# SCH_MinijetengineECU_20260723.net
KiCad netlist of a schematic drawn in EasyEDA
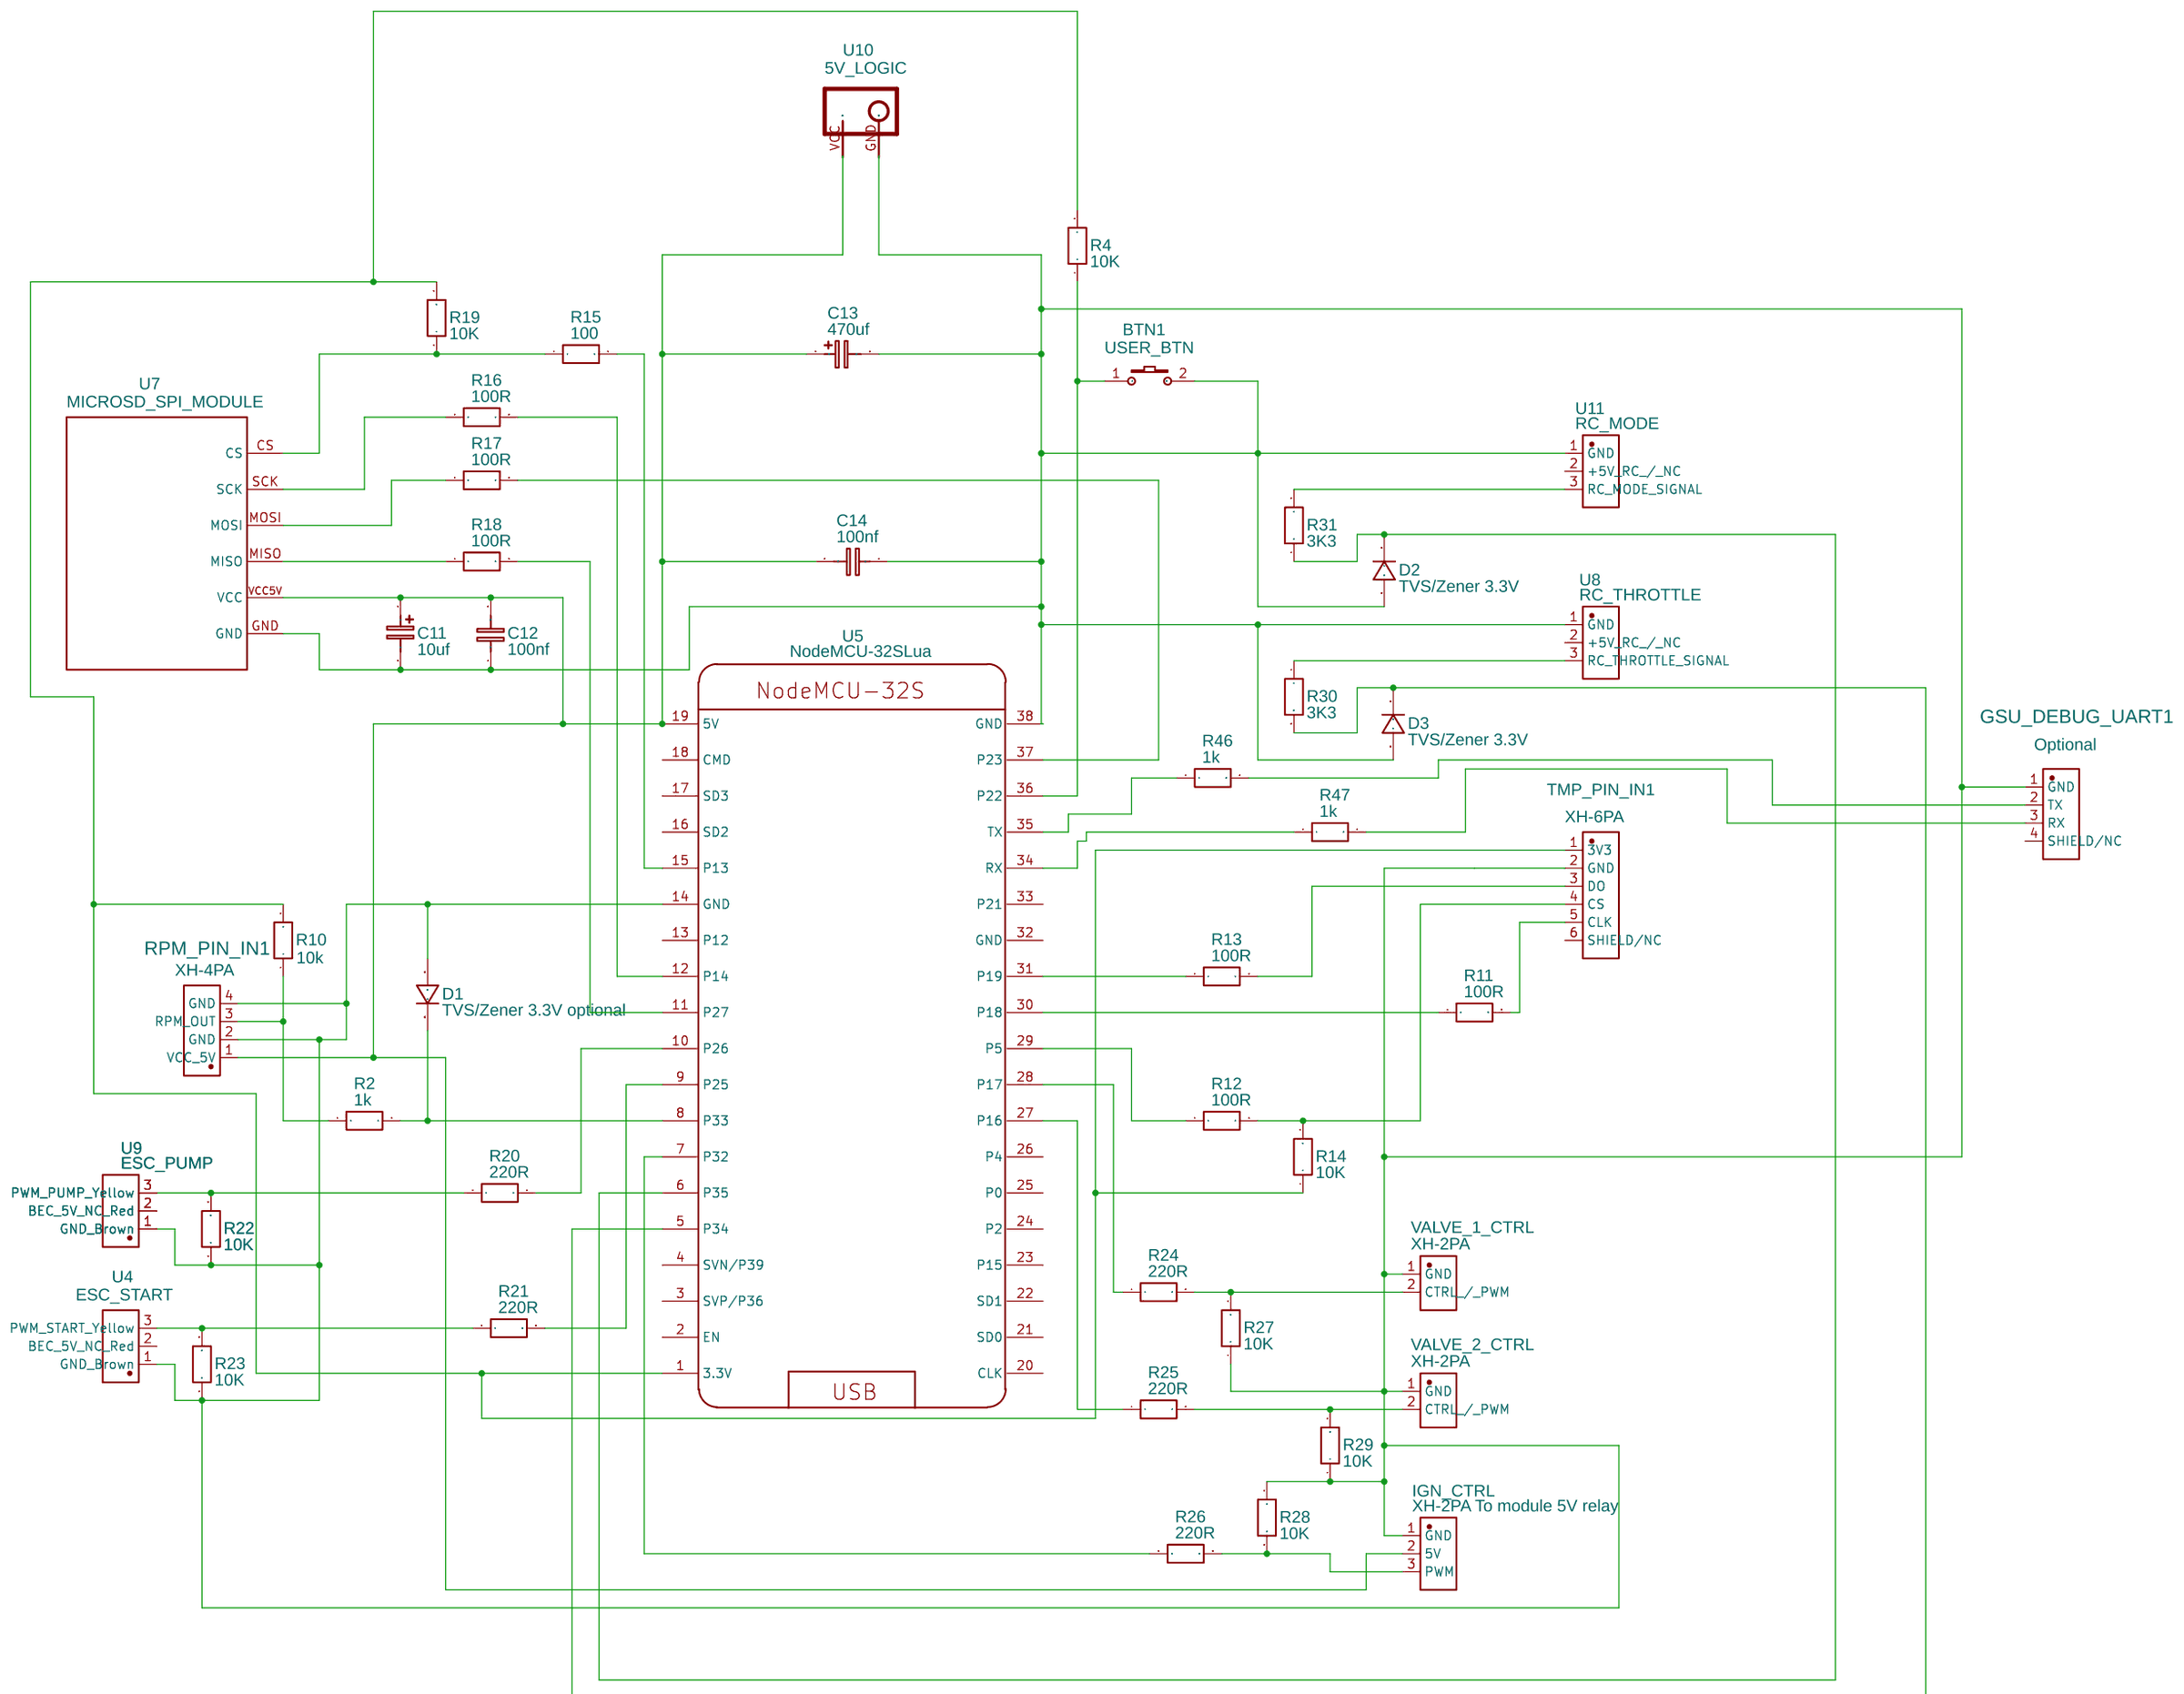
[diagram p0: ECU_JET]
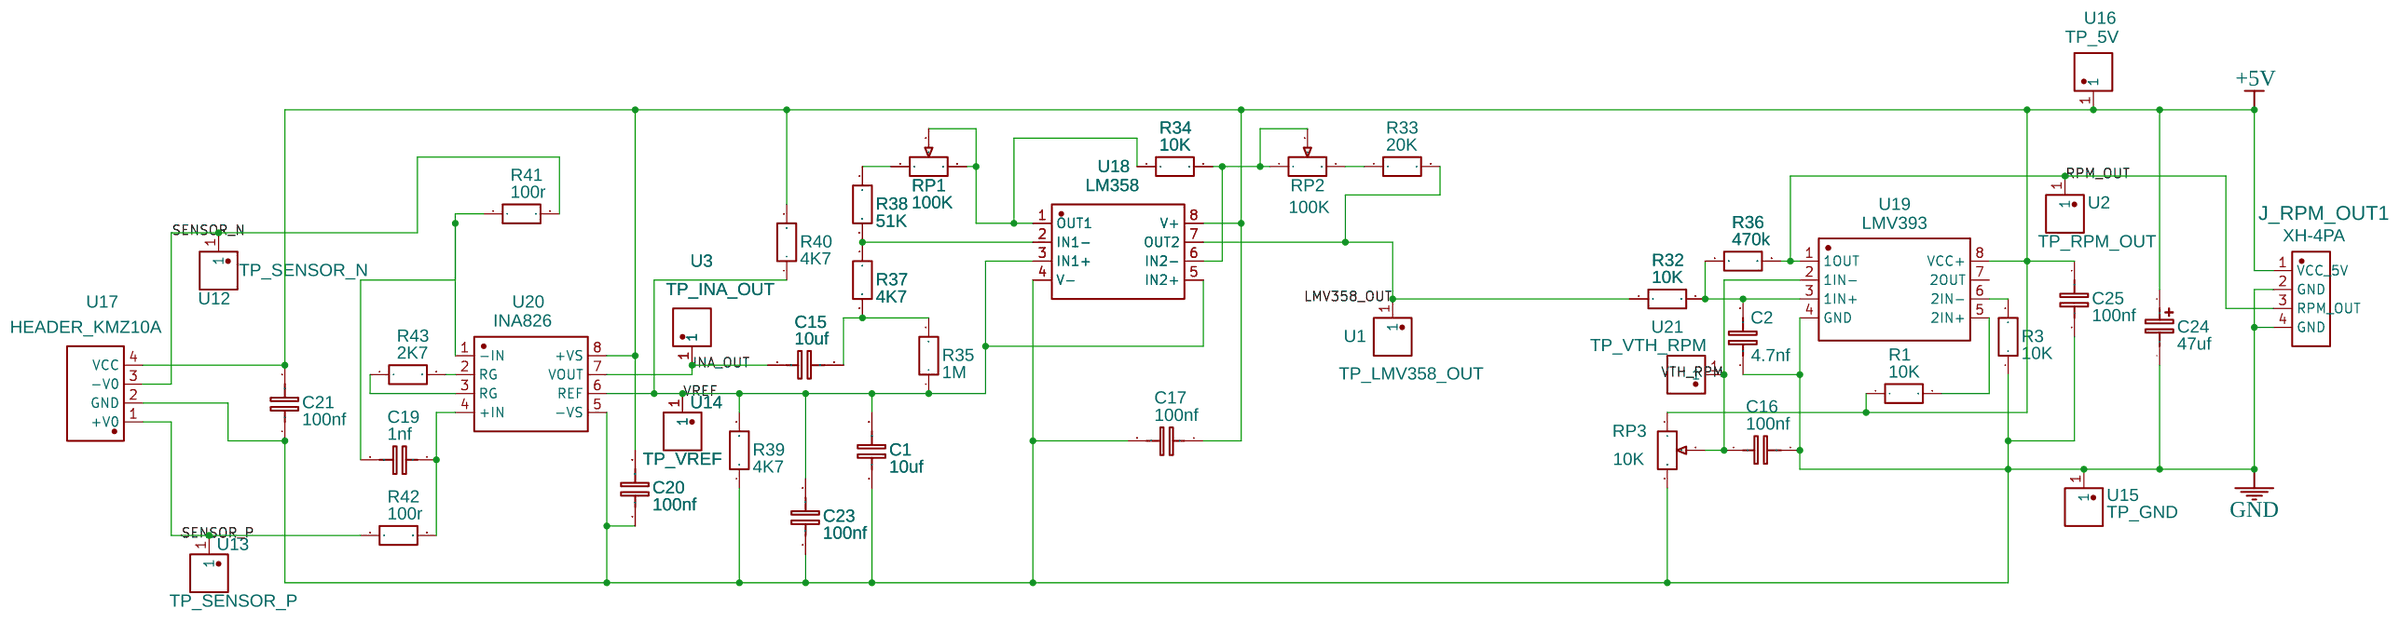
[diagram p1: RPM_Sensor]
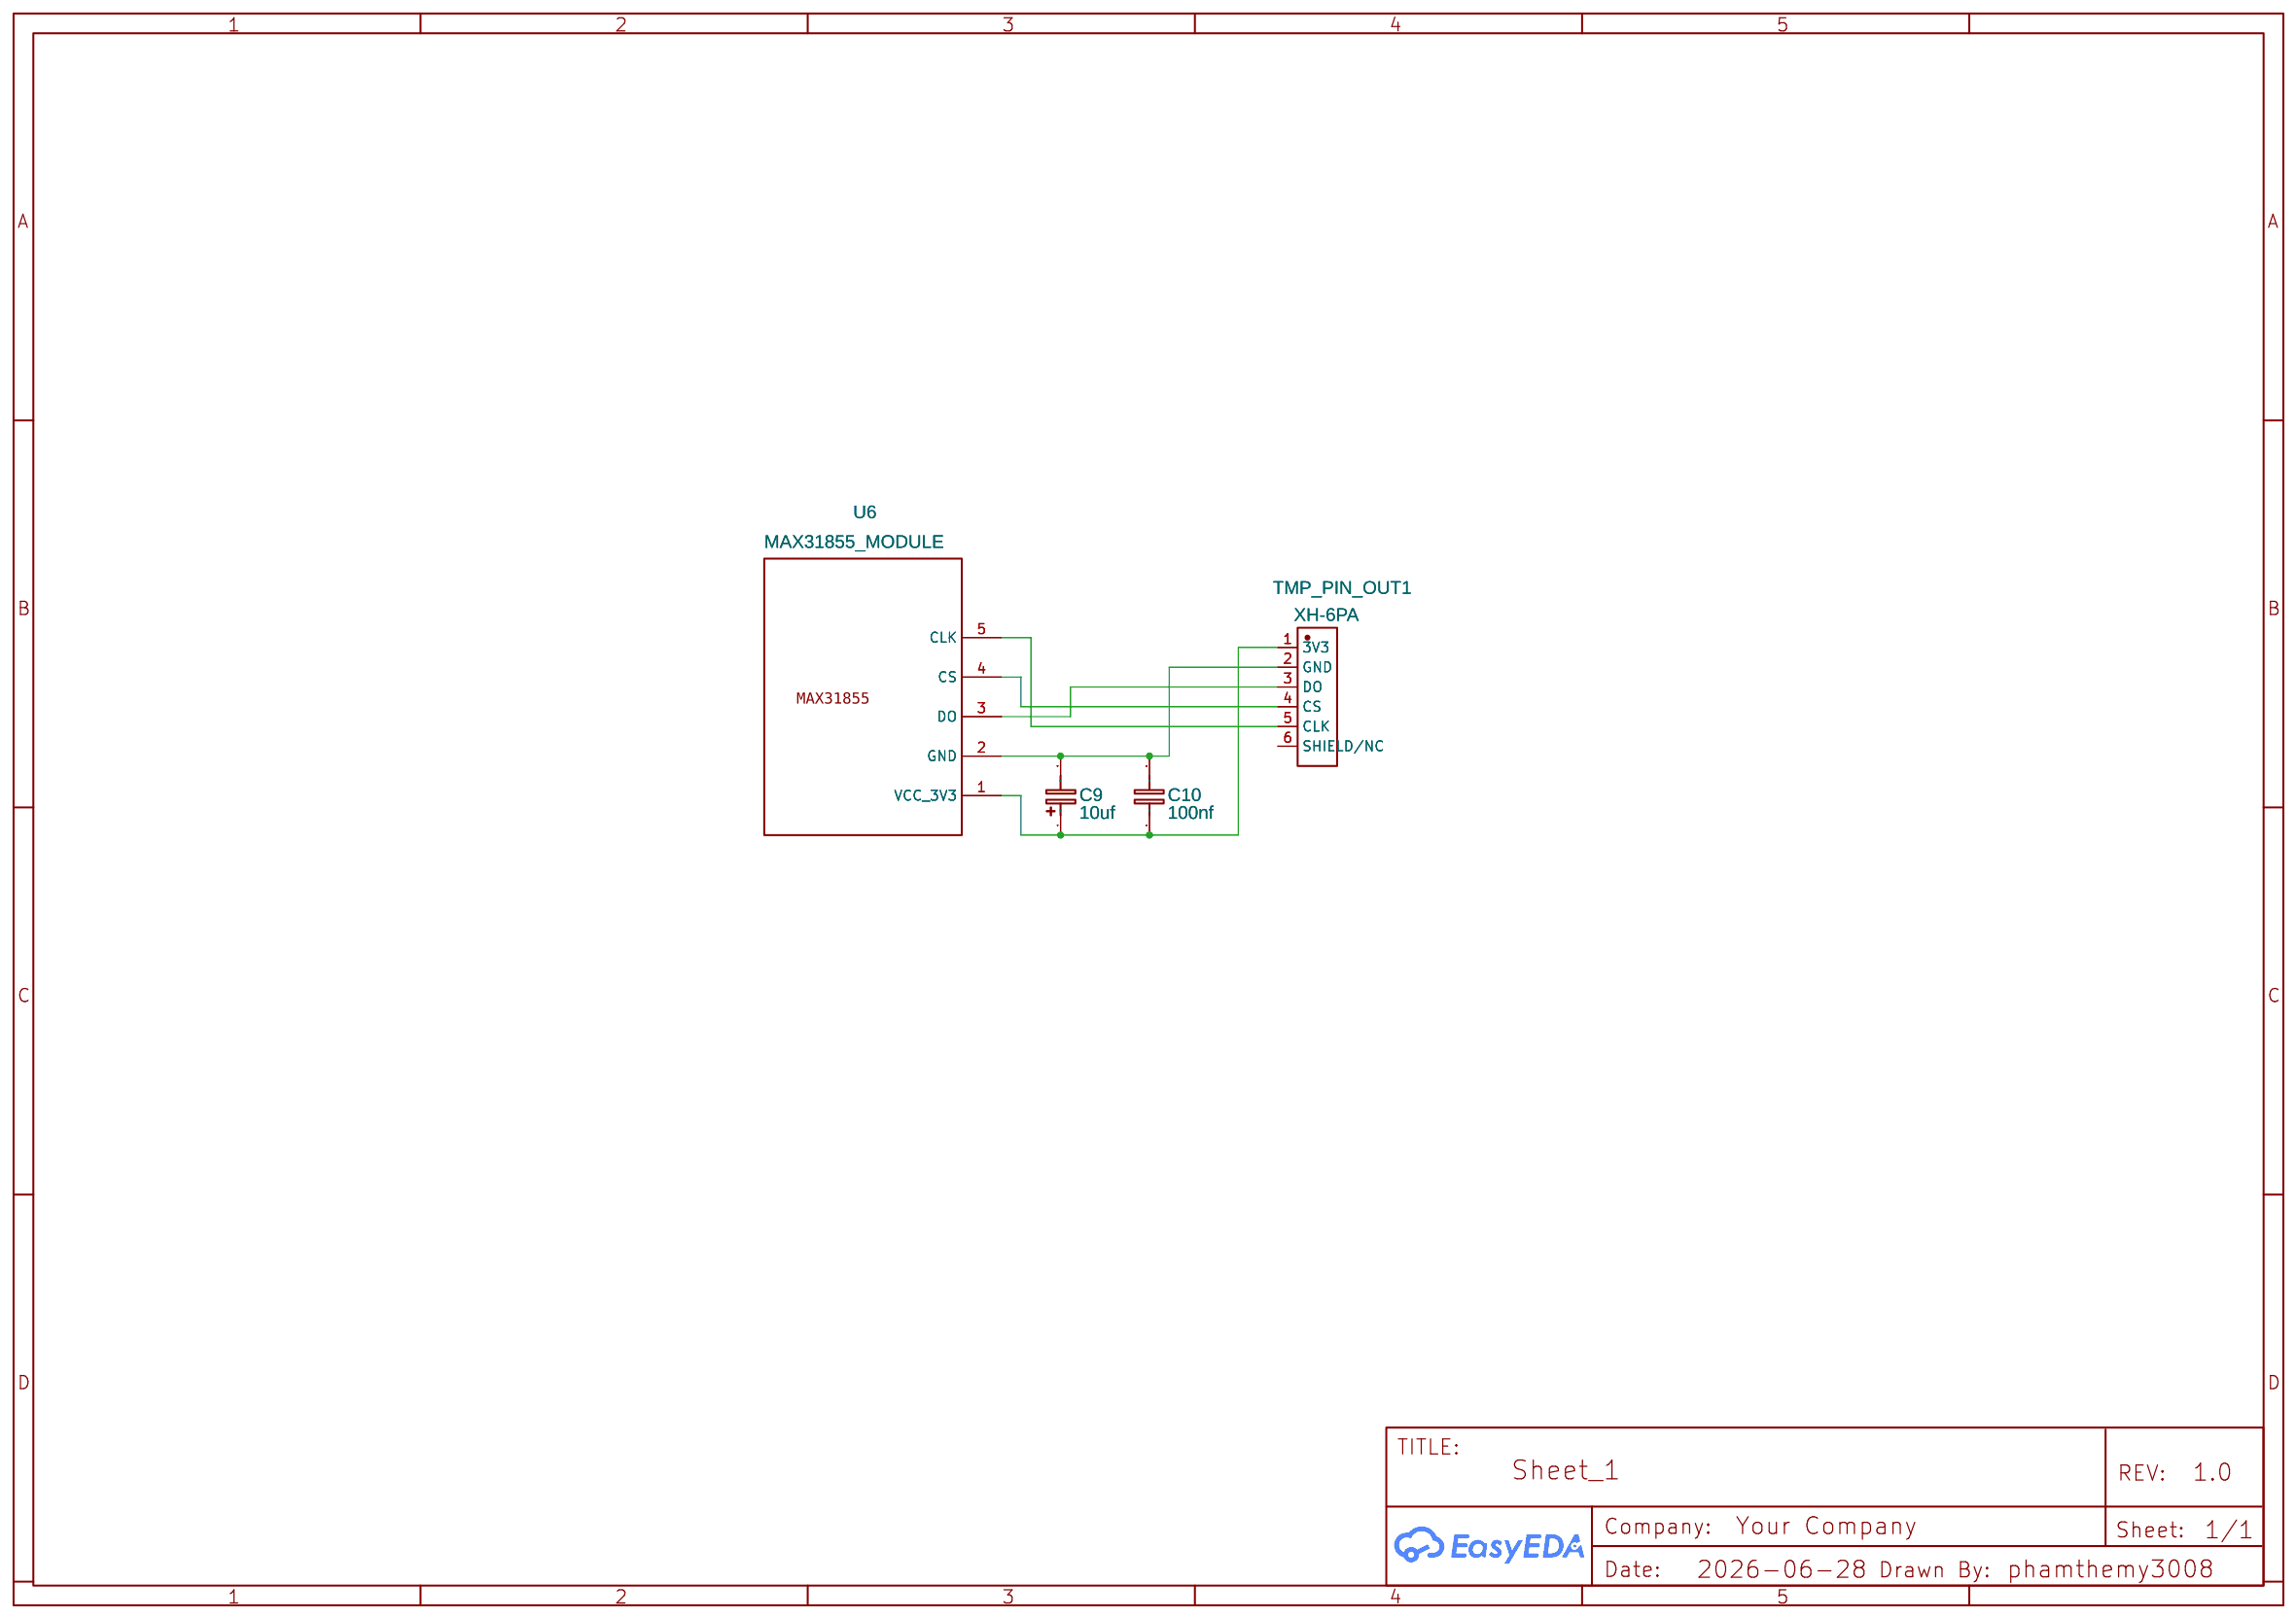
[diagram p2: Temperature_Sensor]

(export (version "E")
  (design (tool "Eeschema 10.0.6"))
  (components
    (comp (ref "BTN1")
      (value "USER_BTN")
      (fields (field (name "Manufacturer Part") "K2-1107ST-A4SW-06"))
      (libsource (lib "") (part "K2-3.6×6.1_SMD"))
    )
    (comp (ref "C11") (value "10uf") (libsource (lib "") (part "C_Tan_SMD_A_EU")))
    (comp (ref "C12") (value "100nf") (libsource (lib "") (part "C_0603_EU")))
    (comp (ref "C13") (value "470uf") (libsource (lib "") (part "C_Tan_SMD_A_EU_1")))
    (comp (ref "C14") (value "100nf") (libsource (lib "") (part "C_0603_EU_1")))
    (comp (ref "D1") (value "TVS/Zener 3.3V optional") (libsource (lib "") (part "1N4007W_1")))
    (comp (ref "D2") (value "TVS/Zener 3.3V") (libsource (lib "") (part "1N4007W")))
    (comp (ref "D3") (value "TVS/Zener 3.3V") (libsource (lib "") (part "1N4007W")))
    (comp (ref "GSU_DEBUG_UART1")
      (value "Optional")
      (fields (field (name "Manufacturer Part") "XH-4PA") (field (name "Manufacturer") "ZHOURI(洲日)"))
      (libsource (lib "") (part "XH-4PA"))
    )
    (comp (ref "IGN_CTRL")
      (value "XH-2PA To module 5V relay")
      (fields (field (name "Manufacturer Part") "Header35.08-3P"))
      (libsource (lib "") (part "HEADER35.08-3P_1"))
    )
    (comp (ref "R2") (value "1k") (libsource (lib "") (part "R_0603_EU")))
    (comp (ref "R4") (value "10K") (libsource (lib "") (part "R_0603_EU_2")))
    (comp (ref "R10") (value "10k") (libsource (lib "") (part "R_0603_EU_2")))
    (comp (ref "R11") (value "100R") (libsource (lib "") (part "R_0603_EU")))
    (comp (ref "R12") (value "100R") (libsource (lib "") (part "R_0603_EU")))
    (comp (ref "R13") (value "100R") (libsource (lib "") (part "R_0603_EU")))
    (comp (ref "R14") (value "10K") (libsource (lib "") (part "R_0603_EU_2")))
    (comp (ref "R15") (value "100") (libsource (lib "") (part "R_0603_EU")))
    (comp (ref "R16") (value "100R") (libsource (lib "") (part "R_0603_EU")))
    (comp (ref "R17") (value "100R") (libsource (lib "") (part "R_0603_EU")))
    (comp (ref "R18") (value "100R") (libsource (lib "") (part "R_0603_EU")))
    (comp (ref "R19") (value "10K") (libsource (lib "") (part "R_0603_EU_2")))
    (comp (ref "R20") (value "220R") (libsource (lib "") (part "R_0603_EU")))
    (comp (ref "R21") (value "220R") (libsource (lib "") (part "R_0603_EU")))
    (comp (ref "R22") (value "10K") (libsource (lib "") (part "R_0603_EU_2")))
    (comp (ref "R23") (value "10K") (libsource (lib "") (part "R_0603_EU_2")))
    (comp (ref "R24") (value "220R") (libsource (lib "") (part "R_0603_EU")))
    (comp (ref "R25") (value "220R") (libsource (lib "") (part "R_0603_EU")))
    (comp (ref "R26") (value "220R") (libsource (lib "") (part "R_0603_EU")))
    (comp (ref "R27") (value "10K") (libsource (lib "") (part "R_0603_EU_2")))
    (comp (ref "R28") (value "10K") (libsource (lib "") (part "R_0603_EU_1")))
    (comp (ref "R29") (value "10K") (libsource (lib "") (part "R_0603_EU_2")))
    (comp (ref "R30") (value "3K3") (libsource (lib "") (part "R_0603_EU_1")))
    (comp (ref "R31") (value "3K3") (libsource (lib "") (part "R_0603_EU_2")))
    (comp (ref "R46") (value "1k") (libsource (lib "") (part "R_0603_EU")))
    (comp (ref "R47") (value "1k") (libsource (lib "") (part "R_0603_EU")))
    (comp (ref "RPM_PIN_IN1")
      (value "XH-4PA")
      (fields (field (name "Manufacturer") "ZHOURI(洲日)"))
      (libsource (lib "") (part "XH-4PA_1"))
    )
    (comp (ref "TMP_PIN_IN1")
      (value "XH-6PA")
      (fields (field (name "Manufacturer") "ZHOURI(洲日)"))
      (libsource (lib "") (part "XH-6PA"))
    )
    (comp (ref "U4")
      (value "ESC_START")
      (fields (field (name "Manufacturer Part") "Header35.08-3P"))
      (libsource (lib "") (part "HEADER35.08-3P"))
    )
    (comp (ref "U5")
      (value "NodeMCU-32SLua")
      (fields (field (name "Manufacturer") "Ai-Thinker"))
      (libsource (lib "") (part "NodeMCU-32SLua"))
    )
    (comp (ref "U7") (value "MICROSD_SPI_MODULE") (libsource (lib "") (part "MICROSD_SPI_MODULE")))
    (comp (ref "U8")
      (value "RC_THROTTLE")
      (fields (field (name "Manufacturer Part") "Header35.08-3P"))
      (libsource (lib "") (part "HEADER35.08-3P_2"))
    )
    (comp (ref "U9")
      (value "ESC_PUMP")
      (fields (field (name "Manufacturer Part") "Header35.08-3P"))
      (libsource (lib "") (part "HEADER35.08-3P_3"))
    )
    (comp (ref "U10") (value "5V_LOGIC") (libsource (lib "") (part "DOMINO-2P-5.08")))
    (comp (ref "U11")
      (value "RC_MODE")
      (fields (field (name "Manufacturer Part") "Header35.08-3P"))
      (libsource (lib "") (part "HEADER35.08-3P_4"))
    )
    (comp (ref "VALVE_1_CTRL")
      (value "XH-2PA")
      (fields (field (name "Manufacturer") "ZHOURI(洲日)"))
      (libsource (lib "") (part "XH-2PA_1"))
    )
    (comp (ref "VALVE_2_CTRL")
      (value "XH-2PA")
      (fields (field (name "Manufacturer") "ZHOURI(洲日)"))
      (libsource (lib "") (part "XH-2PA"))
    )
    (comp (ref "C1") (value "10uf") (libsource (lib "") (part "C_0603_EU_2")))
    (comp (ref "C2") (value "4.7nf") (libsource (lib "") (part "C_0603_EU_6")))
    (comp (ref "C15") (value "10uf") (libsource (lib "") (part "C_0603_EU_3")))
    (comp (ref "C16") (value "100nf") (libsource (lib "") (part "C_0603_EU")))
    (comp (ref "C17") (value "100nf") (libsource (lib "") (part "C_0603_EU_4")))
    (comp (ref "C19") (value "1nf") (libsource (lib "") (part "C_0603_EU_5")))
    (comp (ref "C20") (value "100nf") (libsource (lib "") (part "C_0603_EU_2")))
    (comp (ref "C21") (value "100nf") (libsource (lib "") (part "C_0603_EU_2")))
    (comp (ref "C23") (value "100nf") (libsource (lib "") (part "C_0603_EU_2")))
    (comp (ref "C24")
      (value "47uf")
      (fields (field (name "Manufacturer Part") "TAJB476K010RNJ") (field (name "Manufacturer") "Kyocera AVX"))
      (libsource (lib "") (part "C_Tan_SMD_A_EU"))
    )
    (comp (ref "C25") (value "100nf") (libsource (lib "") (part "C_0603_EU_1")))
    (comp (ref "J_RPM_OUT1")
      (value "XH-4PA")
      (fields (field (name "Manufacturer") "ZHOURI(洲日)"))
      (libsource (lib "") (part "XH-4PA"))
    )
    (comp (ref "R1") (value "10K") (libsource (lib "") (part "R_0603_EU")))
    (comp (ref "R3") (value "10K") (libsource (lib "") (part "R_0603_EU_1")))
    (comp (ref "R32") (value "10K") (libsource (lib "") (part "R_0603_EU")))
    (comp (ref "R33") (value "20K") (libsource (lib "") (part "R_0603_EU")))
    (comp (ref "R34") (value "10K") (libsource (lib "") (part "R_0603_EU")))
    (comp (ref "R35") (value "1M") (libsource (lib "") (part "R_0603_EU_1")))
    (comp (ref "R36") (value "470k") (libsource (lib "") (part "R_0603_EU")))
    (comp (ref "R37") (value "4K7") (libsource (lib "") (part "R_0603_EU_2")))
    (comp (ref "R38") (value "51K") (libsource (lib "") (part "R_0603_EU_2")))
    (comp (ref "R39") (value "4K7") (libsource (lib "") (part "R_0603_EU_1")))
    (comp (ref "R40") (value "4K7") (libsource (lib "") (part "R_0603_EU_1")))
    (comp (ref "R41") (value "100r") (libsource (lib "") (part "R_0603_EU")))
    (comp (ref "R42") (value "100r") (libsource (lib "") (part "R_0603_EU")))
    (comp (ref "R43") (value "2K7") (libsource (lib "") (part "R_0603_EU")))
    (comp (ref "RP1") (value "100K") (libsource (lib "") (part "R_3386P_EU")))
    (comp (ref "RP2") (value "100K") (libsource (lib "") (part "R_3386P_EU")))
    (comp (ref "RP3") (value "10K") (libsource (lib "") (part "R_3386P_EU_1")))
    (comp (ref "U1")
      (value "TP_LMV358_OUT")
      (fields
        (field (name "Manufacturer Part") "YZP0352-20095-01")
        (field (name "Manufacturer") "Xinyangze(鑫扬泽)")
      )
      (libsource (lib "") (part "YZP0352-20095-01"))
    )
    (comp (ref "U2")
      (value "TP_RPM_OUT")
      (fields
        (field (name "Manufacturer Part") "YZP0352-20095-01")
        (field (name "Manufacturer") "Xinyangze(鑫扬泽)")
      )
      (libsource (lib "") (part "YZP0352-20095-01"))
    )
    (comp (ref "U3")
      (value "TP_INA_OUT")
      (fields
        (field (name "Manufacturer Part") "YZP0352-20095-01")
        (field (name "Manufacturer") "Xinyangze(鑫扬泽)")
      )
      (libsource (lib "") (part "YZP0352-20095-01_1"))
    )
    (comp (ref "U12")
      (value "TP_SENSOR_N")
      (fields
        (field (name "Manufacturer Part") "YZP0352-20095-01")
        (field (name "Manufacturer") "Xinyangze(鑫扬泽)")
      )
      (libsource (lib "") (part "YZP0352-20095-01"))
    )
    (comp (ref "U13")
      (value "TP_SENSOR_P")
      (fields
        (field (name "Manufacturer Part") "YZP0352-20095-01")
        (field (name "Manufacturer") "Xinyangze(鑫扬泽)")
      )
      (libsource (lib "") (part "YZP0352-20095-01"))
    )
    (comp (ref "U14")
      (value "TP_VREF")
      (fields
        (field (name "Manufacturer Part") "YZP0352-20095-01")
        (field (name "Manufacturer") "Xinyangze(鑫扬泽)")
      )
      (libsource (lib "") (part "YZP0352-20095-01"))
    )
    (comp (ref "U15")
      (value "TP_GND")
      (fields
        (field (name "Manufacturer Part") "YZP0352-20095-01")
        (field (name "Manufacturer") "Xinyangze(鑫扬泽)")
      )
      (libsource (lib "") (part "YZP0352-20095-01"))
    )
    (comp (ref "U16")
      (value "TP_5V")
      (fields
        (field (name "Manufacturer Part") "YZP0352-20095-01")
        (field (name "Manufacturer") "Xinyangze(鑫扬泽)")
      )
      (libsource (lib "") (part "YZP0352-20095-01_1"))
    )
    (comp (ref "U17") (value "HEADER_KMZ10A") (libsource (lib "") (part "Magnetic Sensor")))
    (comp (ref "U18")
      (value "LM358")
      (fields (field (name "Manufacturer Part") "LMV358") (field (name "Manufacturer") "TECH PUBLIC"))
      (libsource (lib "") (part "LM358DGKRG"))
    )
    (comp (ref "U19")
      (value "LMV393")
      (fields (field (name "Manufacturer Part") "LMV393IDR") (field (name "Manufacturer") "TI(德州仪器)"))
      (libsource (lib "") (part "LMV393IDR"))
    )
    (comp (ref "U20")
      (value "INA826")
      (fields (field (name "Manufacturer Part") "INA826AID") (field (name "Manufacturer") "TI(德州仪器)"))
      (libsource (lib "") (part "INA826AID"))
    )
    (comp (ref "U21")
      (value "TP_VTH_RPM")
      (fields
        (field (name "Manufacturer Part") "YZP0352-20095-01")
        (field (name "Manufacturer") "Xinyangze(鑫扬泽)")
      )
      (libsource (lib "") (part "YZP0352-20095-01_2"))
    )
    (comp (ref "C9") (value "10uf") (libsource (lib "") (part "C_Tan_SMD_A_EU")))
    (comp (ref "C10") (value "100nf") (libsource (lib "") (part "C_0603_EU")))
    (comp (ref "TMP_PIN_OUT1")
      (value "XH-6PA")
      (fields (field (name "Manufacturer") "ZHOURI(洲日)"))
      (libsource (lib "") (part "XH-6PA"))
    )
    (comp (ref "U6") (value "MAX31855_MODULE") (libsource (lib "") (part "MAX31855_MODULE")))
  )
  (nets
    (net (code "1") (name "+5V") (class "Default")
      (node (ref "C17") (pin "1") (pinfunction "1_1") (pintype "unspecified"))
      (node (ref "C20") (pin "2") (pinfunction "2_2") (pintype "unspecified"))
      (node (ref "C21") (pin "2") (pinfunction "2_2") (pintype "unspecified"))
      (node (ref "C24") (pin "+") (pinfunction "1_+") (pintype "unspecified"))
      (node (ref "C25") (pin "1") (pinfunction "2_1") (pintype "unspecified"))
      (node (ref "J_RPM_OUT1") (pin "1") (pinfunction "VCC_5V_1") (pintype "unspecified"))
      (node (ref "R1") (pin "1") (pinfunction "1_1") (pintype "unspecified"))
      (node (ref "R40") (pin "2") (pinfunction "2_2") (pintype "unspecified"))
      (node (ref "RP3") (pin "1") (pinfunction "1_1") (pintype "input"))
      (node (ref "U16") (pin "1") (pinfunction "1_1") (pintype "unspecified"))
      (node (ref "U17") (pin "4") (pinfunction "VCC_4") (pintype "unspecified"))
      (node (ref "U18") (pin "8") (pinfunction "V+_8") (pintype "unspecified"))
      (node (ref "U19") (pin "8") (pinfunction "VCC+_8") (pintype "unspecified"))
      (node (ref "U20") (pin "8") (pinfunction "+VS_8") (pintype "unspecified"))
    )
    (net (code "2") (name "GND") (class "Default")
      (node (ref "C1") (pin "1") (pinfunction "1_1") (pintype "unspecified"))
      (node (ref "C16") (pin "2") (pinfunction "2_2") (pintype "unspecified"))
      (node (ref "C17") (pin "2") (pinfunction "2_2") (pintype "unspecified"))
      (node (ref "C2") (pin "1") (pinfunction "1_1") (pintype "unspecified"))
      (node (ref "C20") (pin "1") (pinfunction "1_1") (pintype "unspecified"))
      (node (ref "C21") (pin "1") (pinfunction "1_1") (pintype "unspecified"))
      (node (ref "C23") (pin "1") (pinfunction "1_1") (pintype "unspecified"))
      (node (ref "C24") (pin "-") (pinfunction "2_-") (pintype "unspecified"))
      (node (ref "C25") (pin "2") (pinfunction "1_2") (pintype "unspecified"))
      (node (ref "J_RPM_OUT1") (pin "2") (pinfunction "GND_2") (pintype "unspecified"))
      (node (ref "J_RPM_OUT1") (pin "4") (pinfunction "GND_4") (pintype "unspecified"))
      (node (ref "R3") (pin "1") (pinfunction "1_1") (pintype "unspecified"))
      (node (ref "R39") (pin "1") (pinfunction "1_1") (pintype "unspecified"))
      (node (ref "RP3") (pin "3") (pinfunction "3_3") (pintype "input"))
      (node (ref "U15") (pin "1") (pinfunction "1_1") (pintype "unspecified"))
      (node (ref "U17") (pin "2") (pinfunction "GND_2") (pintype "unspecified"))
      (node (ref "U18") (pin "4") (pinfunction "V-_4") (pintype "unspecified"))
      (node (ref "U19") (pin "4") (pinfunction "GND_4") (pintype "unspecified"))
      (node (ref "U20") (pin "5") (pinfunction "-VS_5") (pintype "unspecified"))
    )
    (net (code "3") (name "INA_OUT") (class "Default")
      (node (ref "C15") (pin "1") (pinfunction "1_1") (pintype "unspecified"))
      (node (ref "U20") (pin "7") (pinfunction "VOUT_7") (pintype "unspecified"))
      (node (ref "U3") (pin "1") (pinfunction "1_1") (pintype "unspecified"))
    )
    (net (code "4") (name "LMV358_OUT") (class "Default")
      (node (ref "R32") (pin "1") (pinfunction "1_1") (pintype "unspecified"))
      (node (ref "R33") (pin "2") (pinfunction "2_2") (pintype "unspecified"))
      (node (ref "U1") (pin "1") (pinfunction "1_1") (pintype "unspecified"))
      (node (ref "U18") (pin "7") (pinfunction "OUT2_7") (pintype "unspecified"))
    )
    (net (code "5") (name "Net-(C15-Pad2)") (class "Default")
      (node (ref "C15") (pin "2") (pinfunction "2_2") (pintype "unspecified"))
      (node (ref "R35") (pin "2") (pinfunction "2_2") (pintype "unspecified"))
      (node (ref "R37") (pin "2") (pinfunction "2_2") (pintype "unspecified"))
    )
    (net (code "6") (name "Net-(D1-1)") (class "Default")
      (node (ref "D1") (pin "P$1") (pinfunction "1_P$1") (pintype "unspecified"))
      (node (ref "R2") (pin "2") (pinfunction "2_2") (pintype "unspecified"))
      (node (ref "U5") (pin "8") (pinfunction "P33_8") (pintype "unspecified"))
    )
    (net (code "7") (name "Net-(D1-2)") (class "Default")
      (node (ref "BTN1") (pin "2") (pinfunction "2_2") (pintype "unspecified"))
      (node (ref "C11") (pin "2") (pinfunction "2_2") (pintype "unspecified"))
      (node (ref "C12") (pin "1") (pinfunction "1_1") (pintype "unspecified"))
      (node (ref "C13") (pin "2") (pinfunction "2_2") (pintype "unspecified"))
      (node (ref "C14") (pin "1") (pinfunction "1_1") (pintype "unspecified"))
      (node (ref "D1") (pin "P$2") (pinfunction "2_P$2") (pintype "unspecified"))
      (node (ref "D2") (pin "P$2") (pinfunction "2_P$2") (pintype "unspecified"))
      (node (ref "D3") (pin "P$2") (pinfunction "2_P$2") (pintype "unspecified"))
      (node (ref "GSU_DEBUG_UART1") (pin "1") (pinfunction "GND_1") (pintype "unspecified"))
      (node (ref "IGN_CTRL") (pin "1") (pinfunction "GND_1") (pintype "unspecified"))
      (node (ref "R22") (pin "1") (pinfunction "1_1") (pintype "unspecified"))
      (node (ref "R23") (pin "1") (pinfunction "1_1") (pintype "unspecified"))
      (node (ref "R27") (pin "1") (pinfunction "1_1") (pintype "unspecified"))
      (node (ref "R28") (pin "1") (pinfunction "1_1") (pintype "unspecified"))
      (node (ref "R29") (pin "1") (pinfunction "1_1") (pintype "unspecified"))
      (node (ref "RPM_PIN_IN1") (pin "2") (pinfunction "GND_2") (pintype "unspecified"))
      (node (ref "RPM_PIN_IN1") (pin "4") (pinfunction "GND_4") (pintype "unspecified"))
      (node (ref "TMP_PIN_IN1") (pin "2") (pinfunction "GND_2") (pintype "unspecified"))
      (node (ref "U10") (pin "GND") (pinfunction "GND_GND") (pintype "passive"))
      (node (ref "U11") (pin "1") (pinfunction "GND_1") (pintype "unspecified"))
      (node (ref "U4") (pin "1") (pinfunction "GND_Brown_1") (pintype "unspecified"))
      (node (ref "U5") (pin "14") (pinfunction "GND_14") (pintype "unspecified"))
      (node (ref "U5") (pin "38") (pinfunction "GND_38") (pintype "unspecified"))
      (node (ref "U7") (pin "GND") (pinfunction "GND_GND") (pintype "input"))
      (node (ref "U8") (pin "1") (pinfunction "GND_1") (pintype "unspecified"))
      (node (ref "U9") (pin "1") (pinfunction "GND_Brown_1") (pintype "unspecified"))
      (node (ref "VALVE_1_CTRL") (pin "1") (pinfunction "GND_1") (pintype "unspecified"))
      (node (ref "VALVE_2_CTRL") (pin "1") (pinfunction "GND_1") (pintype "unspecified"))
    )
    (net (code "8") (name "Net-(D2-1)") (class "Default")
      (node (ref "D2") (pin "P$1") (pinfunction "1_P$1") (pintype "unspecified"))
      (node (ref "R31") (pin "1") (pinfunction "1_1") (pintype "unspecified"))
      (node (ref "U5") (pin "6") (pinfunction "P35_6") (pintype "unspecified"))
    )
    (net (code "9") (name "Net-(D3-1)") (class "Default")
      (node (ref "D3") (pin "P$1") (pinfunction "1_P$1") (pintype "unspecified"))
      (node (ref "R30") (pin "2") (pinfunction "2_2") (pintype "unspecified"))
      (node (ref "U5") (pin "5") (pinfunction "P34_5") (pintype "unspecified"))
    )
    (net (code "10") (name "Net-(GSU_DEBUG_UART1-RX)") (class "Default")
      (node (ref "GSU_DEBUG_UART1") (pin "3") (pinfunction "RX_3") (pintype "unspecified"))
      (node (ref "R47") (pin "2") (pinfunction "2_2") (pintype "unspecified"))
    )
    (net (code "11") (name "Net-(GSU_DEBUG_UART1-TX)") (class "Default")
      (node (ref "GSU_DEBUG_UART1") (pin "2") (pinfunction "TX_2") (pintype "unspecified"))
      (node (ref "R46") (pin "2") (pinfunction "2_2") (pintype "unspecified"))
    )
    (net (code "12") (name "Net-(IGN_CTRL-5V)") (class "Default")
      (node (ref "C11") (pin "1") (pinfunction "1_1") (pintype "unspecified"))
      (node (ref "C12") (pin "2") (pinfunction "2_2") (pintype "unspecified"))
      (node (ref "C13") (pin "1") (pinfunction "1_1") (pintype "unspecified"))
      (node (ref "C14") (pin "2") (pinfunction "2_2") (pintype "unspecified"))
      (node (ref "IGN_CTRL") (pin "2") (pinfunction "5V_2") (pintype "unspecified"))
      (node (ref "RPM_PIN_IN1") (pin "1") (pinfunction "VCC_5V_1") (pintype "unspecified"))
      (node (ref "U10") (pin "VCC") (pinfunction "VCC_VCC") (pintype "passive"))
      (node (ref "U5") (pin "19") (pinfunction "5V_19") (pintype "unspecified"))
      (node (ref "U7") (pin "VCC5V") (pinfunction "VCC_VCC5V") (pintype "input"))
    )
    (net (code "13") (name "Net-(IGN_CTRL-PWM)") (class "Default")
      (node (ref "IGN_CTRL") (pin "3") (pinfunction "PWM_3") (pintype "unspecified"))
      (node (ref "R26") (pin "2") (pinfunction "2_2") (pintype "unspecified"))
      (node (ref "R28") (pin "2") (pinfunction "2_2") (pintype "unspecified"))
    )
    (net (code "14") (name "Net-(R15-Pad1)") (class "Default")
      (node (ref "R15") (pin "1") (pinfunction "1_1") (pintype "unspecified"))
      (node (ref "R19") (pin "1") (pinfunction "1_1") (pintype "unspecified"))
      (node (ref "U7") (pin "CS") (pinfunction "CS_CS") (pintype "bidirectional"))
    )
    (net (code "15") (name "Net-(R16-Pad1)") (class "Default")
      (node (ref "R16") (pin "1") (pinfunction "1_1") (pintype "unspecified"))
      (node (ref "U7") (pin "SCK") (pinfunction "SCK_SCK") (pintype "bidirectional"))
    )
    (net (code "16") (name "Net-(R17-Pad1)") (class "Default")
      (node (ref "R17") (pin "1") (pinfunction "1_1") (pintype "unspecified"))
      (node (ref "U7") (pin "MOSI") (pinfunction "MOSI_MOSI") (pintype "input"))
    )
    (net (code "17") (name "Net-(R18-Pad1)") (class "Default")
      (node (ref "R18") (pin "1") (pinfunction "1_1") (pintype "unspecified"))
      (node (ref "U7") (pin "MISO") (pinfunction "MISO_MISO") (pintype "output"))
    )
    (net (code "18") (name "Net-(R33-Pad1)") (class "Default")
      (node (ref "R33") (pin "1") (pinfunction "1_1") (pintype "unspecified"))
      (node (ref "RP2") (pin "3") (pinfunction "3_3") (pintype "input"))
    )
    (net (code "19") (name "Net-(R38-Pad1)") (class "Default")
      (node (ref "R38") (pin "1") (pinfunction "1_1") (pintype "unspecified"))
      (node (ref "RP1") (pin "1") (pinfunction "1_1") (pintype "input"))
    )
    (net (code "20") (name "Net-(R43-Pad1)") (class "Default")
      (node (ref "R43") (pin "1") (pinfunction "1_1") (pintype "unspecified"))
      (node (ref "U20") (pin "3") (pinfunction "RG_3") (pintype "unspecified"))
    )
    (net (code "21") (name "Net-(R43-Pad2)") (class "Default")
      (node (ref "R43") (pin "2") (pinfunction "2_2") (pintype "unspecified"))
      (node (ref "U20") (pin "2") (pinfunction "RG_2") (pintype "unspecified"))
    )
    (net (code "22") (name "Net-(RPM_PIN_IN1-RPM_OUT)") (class "Default")
      (node (ref "R10") (pin "1") (pinfunction "1_1") (pintype "unspecified"))
      (node (ref "R2") (pin "1") (pinfunction "1_1") (pintype "unspecified"))
      (node (ref "RPM_PIN_IN1") (pin "3") (pinfunction "RPM_OUT_3") (pintype "unspecified"))
    )
    (net (code "23") (name "Net-(TMP_PIN_IN1-3V3)") (class "Default")
      (node (ref "R10") (pin "2") (pinfunction "2_2") (pintype "unspecified"))
      (node (ref "R14") (pin "1") (pinfunction "1_1") (pintype "unspecified"))
      (node (ref "R19") (pin "2") (pinfunction "2_2") (pintype "unspecified"))
      (node (ref "R4") (pin "2") (pinfunction "2_2") (pintype "unspecified"))
      (node (ref "TMP_PIN_IN1") (pin "1") (pinfunction "3V3_1") (pintype "unspecified"))
      (node (ref "U5") (pin "1") (pinfunction "3.3V_1") (pintype "unspecified"))
    )
    (net (code "24") (name "Net-(TMP_PIN_IN1-CLK)") (class "Default")
      (node (ref "R11") (pin "2") (pinfunction "2_2") (pintype "unspecified"))
      (node (ref "TMP_PIN_IN1") (pin "5") (pinfunction "CLK_5") (pintype "unspecified"))
    )
    (net (code "25") (name "Net-(TMP_PIN_IN1-CS)") (class "Default")
      (node (ref "R12") (pin "2") (pinfunction "2_2") (pintype "unspecified"))
      (node (ref "R14") (pin "2") (pinfunction "2_2") (pintype "unspecified"))
      (node (ref "TMP_PIN_IN1") (pin "4") (pinfunction "CS_4") (pintype "unspecified"))
    )
    (net (code "26") (name "Net-(TMP_PIN_IN1-DO)") (class "Default")
      (node (ref "R13") (pin "2") (pinfunction "2_2") (pintype "unspecified"))
      (node (ref "TMP_PIN_IN1") (pin "3") (pinfunction "DO_3") (pintype "unspecified"))
    )
    (net (code "27") (name "Net-(TMP_PIN_OUT1-3V3)") (class "Default")
      (node (ref "C10") (pin "1") (pinfunction "1_1") (pintype "unspecified"))
      (node (ref "C9") (pin "1") (pinfunction "1_1") (pintype "unspecified"))
      (node (ref "TMP_PIN_OUT1") (pin "1") (pinfunction "3V3_1") (pintype "passive"))
      (node (ref "U6") (pin "1") (pinfunction "VCC_3V3_1") (pintype "bidirectional"))
    )
    (net (code "28") (name "Net-(TMP_PIN_OUT1-CLK)") (class "Default")
      (node (ref "TMP_PIN_OUT1") (pin "5") (pinfunction "CLK_5") (pintype "unspecified"))
      (node (ref "U6") (pin "5") (pinfunction "CLK_5") (pintype "output"))
    )
    (net (code "29") (name "Net-(TMP_PIN_OUT1-CS)") (class "Default")
      (node (ref "TMP_PIN_OUT1") (pin "4") (pinfunction "CS_4") (pintype "unspecified"))
      (node (ref "U6") (pin "4") (pinfunction "CS_4") (pintype "input"))
    )
    (net (code "30") (name "Net-(TMP_PIN_OUT1-DO)") (class "Default")
      (node (ref "TMP_PIN_OUT1") (pin "3") (pinfunction "DO_3") (pintype "output"))
      (node (ref "U6") (pin "3") (pinfunction "DO_3") (pintype "input"))
    )
    (net (code "31") (name "Net-(TMP_PIN_OUT1-GND)") (class "Default")
      (node (ref "C10") (pin "2") (pinfunction "2_2") (pintype "unspecified"))
      (node (ref "C9") (pin "2") (pinfunction "2_2") (pintype "unspecified"))
      (node (ref "TMP_PIN_OUT1") (pin "2") (pinfunction "GND_2") (pintype "passive"))
      (node (ref "U6") (pin "2") (pinfunction "GND_2") (pintype "bidirectional"))
    )
    (net (code "32") (name "Net-(U4-PWM_START_Yellow)") (class "Default")
      (node (ref "R21") (pin "1") (pinfunction "1_1") (pintype "unspecified"))
      (node (ref "R23") (pin "2") (pinfunction "2_2") (pintype "unspecified"))
      (node (ref "U4") (pin "3") (pinfunction "PWM_START_Yellow_3") (pintype "unspecified"))
    )
    (net (code "33") (name "Net-(U5-P5)") (class "Default")
      (node (ref "R12") (pin "1") (pinfunction "1_1") (pintype "unspecified"))
      (node (ref "U5") (pin "29") (pinfunction "P5_29") (pintype "unspecified"))
    )
    (net (code "34") (name "Net-(U5-P13)") (class "Default")
      (node (ref "R15") (pin "2") (pinfunction "2_2") (pintype "unspecified"))
      (node (ref "U5") (pin "15") (pinfunction "P13_15") (pintype "unspecified"))
    )
    (net (code "35") (name "Net-(U5-P14)") (class "Default")
      (node (ref "R16") (pin "2") (pinfunction "2_2") (pintype "unspecified"))
      (node (ref "U5") (pin "12") (pinfunction "P14_12") (pintype "unspecified"))
    )
    (net (code "36") (name "Net-(U5-P16)") (class "Default")
      (node (ref "R25") (pin "1") (pinfunction "1_1") (pintype "unspecified"))
      (node (ref "U5") (pin "27") (pinfunction "P16_27") (pintype "unspecified"))
    )
    (net (code "37") (name "Net-(U5-P17)") (class "Default")
      (node (ref "R24") (pin "1") (pinfunction "1_1") (pintype "unspecified"))
      (node (ref "U5") (pin "28") (pinfunction "P17_28") (pintype "unspecified"))
    )
    (net (code "38") (name "Net-(U5-P18)") (class "Default")
      (node (ref "R11") (pin "1") (pinfunction "1_1") (pintype "unspecified"))
      (node (ref "U5") (pin "30") (pinfunction "P18_30") (pintype "unspecified"))
    )
    (net (code "39") (name "Net-(U5-P19)") (class "Default")
      (node (ref "R13") (pin "1") (pinfunction "1_1") (pintype "unspecified"))
      (node (ref "U5") (pin "31") (pinfunction "P19_31") (pintype "unspecified"))
    )
    (net (code "40") (name "Net-(U5-P22)") (class "Default")
      (node (ref "BTN1") (pin "1") (pinfunction "1_1") (pintype "unspecified"))
      (node (ref "R4") (pin "1") (pinfunction "1_1") (pintype "unspecified"))
      (node (ref "U5") (pin "36") (pinfunction "P22_36") (pintype "unspecified"))
    )
    (net (code "41") (name "Net-(U5-P23)") (class "Default")
      (node (ref "R17") (pin "2") (pinfunction "2_2") (pintype "unspecified"))
      (node (ref "U5") (pin "37") (pinfunction "P23_37") (pintype "unspecified"))
    )
    (net (code "42") (name "Net-(U5-P25)") (class "Default")
      (node (ref "R21") (pin "2") (pinfunction "2_2") (pintype "unspecified"))
      (node (ref "U5") (pin "9") (pinfunction "P25_9") (pintype "unspecified"))
    )
    (net (code "43") (name "Net-(U5-P26)") (class "Default")
      (node (ref "R20") (pin "2") (pinfunction "2_2") (pintype "unspecified"))
      (node (ref "U5") (pin "10") (pinfunction "P26_10") (pintype "unspecified"))
    )
    (net (code "44") (name "Net-(U5-P27)") (class "Default")
      (node (ref "R18") (pin "2") (pinfunction "2_2") (pintype "unspecified"))
      (node (ref "U5") (pin "11") (pinfunction "P27_11") (pintype "unspecified"))
    )
    (net (code "45") (name "Net-(U5-P32)") (class "Default")
      (node (ref "R26") (pin "1") (pinfunction "1_1") (pintype "unspecified"))
      (node (ref "U5") (pin "7") (pinfunction "P32_7") (pintype "unspecified"))
    )
    (net (code "46") (name "Net-(U5-RX)") (class "Default")
      (node (ref "R47") (pin "1") (pinfunction "1_1") (pintype "unspecified"))
      (node (ref "U5") (pin "34") (pinfunction "RX_34") (pintype "unspecified"))
    )
    (net (code "47") (name "Net-(U5-TX)") (class "Default")
      (node (ref "R46") (pin "1") (pinfunction "1_1") (pintype "unspecified"))
      (node (ref "U5") (pin "35") (pinfunction "TX_35") (pintype "unspecified"))
    )
    (net (code "48") (name "Net-(U8-RC_THROTTLE_SIGNAL)") (class "Default")
      (node (ref "R30") (pin "1") (pinfunction "1_1") (pintype "unspecified"))
      (node (ref "U8") (pin "3") (pinfunction "RC_THROTTLE_SIGNAL_3") (pintype "unspecified"))
    )
    (net (code "49") (name "Net-(U9-PWM_PUMP_Yellow)") (class "Default")
      (node (ref "R20") (pin "1") (pinfunction "1_1") (pintype "unspecified"))
      (node (ref "R22") (pin "2") (pinfunction "2_2") (pintype "unspecified"))
      (node (ref "U9") (pin "3") (pinfunction "PWM_PUMP_Yellow_3") (pintype "unspecified"))
    )
    (net (code "50") (name "Net-(U11-RC_MODE_SIGNAL)") (class "Default")
      (node (ref "R31") (pin "2") (pinfunction "2_2") (pintype "unspecified"))
      (node (ref "U11") (pin "3") (pinfunction "RC_MODE_SIGNAL_3") (pintype "unspecified"))
    )
    (net (code "51") (name "Net-(U18-IN1-)") (class "Default")
      (node (ref "R37") (pin "1") (pinfunction "1_1") (pintype "unspecified"))
      (node (ref "R38") (pin "2") (pinfunction "2_2") (pintype "unspecified"))
      (node (ref "U18") (pin "2") (pinfunction "IN1-_2") (pintype "unspecified"))
    )
    (net (code "52") (name "Net-(U18-IN2-)") (class "Default")
      (node (ref "R34") (pin "2") (pinfunction "2_2") (pintype "unspecified"))
      (node (ref "RP2") (pin "1") (pinfunction "1_1") (pintype "input"))
      (node (ref "RP2") (pin "2") (pinfunction "2_2") (pintype "input"))
      (node (ref "U18") (pin "6") (pinfunction "IN2-_6") (pintype "unspecified"))
    )
    (net (code "53") (name "Net-(U18-OUT1)") (class "Default")
      (node (ref "R34") (pin "1") (pinfunction "1_1") (pintype "unspecified"))
      (node (ref "RP1") (pin "2") (pinfunction "2_2") (pintype "input"))
      (node (ref "RP1") (pin "3") (pinfunction "3_3") (pintype "input"))
      (node (ref "U18") (pin "1") (pinfunction "OUT1_1") (pintype "unspecified"))
    )
    (net (code "54") (name "Net-(U19-1IN+)") (class "Default")
      (node (ref "C2") (pin "2") (pinfunction "2_2") (pintype "unspecified"))
      (node (ref "R32") (pin "2") (pinfunction "2_2") (pintype "unspecified"))
      (node (ref "R36") (pin "1") (pinfunction "1_1") (pintype "unspecified"))
      (node (ref "U19") (pin "3") (pinfunction "1IN+_3") (pintype "unspecified"))
    )
    (net (code "55") (name "Net-(U19-2IN+)") (class "Default")
      (node (ref "R1") (pin "2") (pinfunction "2_2") (pintype "unspecified"))
      (node (ref "U19") (pin "5") (pinfunction "2IN+_5") (pintype "unspecified"))
    )
    (net (code "56") (name "Net-(U19-2IN-)") (class "Default")
      (node (ref "R3") (pin "2") (pinfunction "2_2") (pintype "unspecified"))
      (node (ref "U19") (pin "6") (pinfunction "2IN-_6") (pintype "unspecified"))
    )
    (net (code "57") (name "Net-(U20-+IN)") (class "Default")
      (node (ref "C19") (pin "1") (pinfunction "1_1") (pintype "unspecified"))
      (node (ref "R42") (pin "2") (pinfunction "2_2") (pintype "unspecified"))
      (node (ref "U20") (pin "4") (pinfunction "+IN_4") (pintype "unspecified"))
    )
    (net (code "58") (name "Net-(U20--IN)") (class "Default")
      (node (ref "C19") (pin "2") (pinfunction "2_2") (pintype "unspecified"))
      (node (ref "R41") (pin "1") (pinfunction "1_1") (pintype "unspecified"))
      (node (ref "U20") (pin "1") (pinfunction "-IN_1") (pintype "unspecified"))
    )
    (net (code "59") (name "Net-(VALVE_1_CTRL-CTRL_{slash}_PWM)") (class "Default")
      (node (ref "R24") (pin "2") (pinfunction "2_2") (pintype "unspecified"))
      (node (ref "R27") (pin "2") (pinfunction "2_2") (pintype "unspecified"))
      (node (ref "VALVE_1_CTRL") (pin "2") (pinfunction "CTRL_/_PWM_2") (pintype "unspecified"))
    )
    (net (code "60") (name "Net-(VALVE_2_CTRL-CTRL_{slash}_PWM)") (class "Default")
      (node (ref "R25") (pin "2") (pinfunction "2_2") (pintype "unspecified"))
      (node (ref "R29") (pin "2") (pinfunction "2_2") (pintype "unspecified"))
      (node (ref "VALVE_2_CTRL") (pin "2") (pinfunction "CTRL_/_PWM_2") (pintype "unspecified"))
    )
    (net (code "61") (name "RPM_OUT") (class "Default")
      (node (ref "J_RPM_OUT1") (pin "3") (pinfunction "RPM_OUT_3") (pintype "unspecified"))
      (node (ref "R36") (pin "2") (pinfunction "2_2") (pintype "unspecified"))
      (node (ref "U19") (pin "1") (pinfunction "1OUT_1") (pintype "unspecified"))
      (node (ref "U2") (pin "1") (pinfunction "1_1") (pintype "unspecified"))
    )
    (net (code "62") (name "SENSOR_N") (class "Default")
      (node (ref "R41") (pin "2") (pinfunction "2_2") (pintype "unspecified"))
      (node (ref "U12") (pin "1") (pinfunction "1_1") (pintype "unspecified"))
      (node (ref "U17") (pin "3") (pinfunction "-V0_3") (pintype "unspecified"))
    )
    (net (code "63") (name "SENSOR_P") (class "Default")
      (node (ref "R42") (pin "1") (pinfunction "1_1") (pintype "unspecified"))
      (node (ref "U13") (pin "1") (pinfunction "1_1") (pintype "unspecified"))
      (node (ref "U17") (pin "1") (pinfunction "+V0_1") (pintype "unspecified"))
    )
    (net (code "64") (name "VREF") (class "Default")
      (node (ref "C1") (pin "2") (pinfunction "2_2") (pintype "unspecified"))
      (node (ref "C23") (pin "2") (pinfunction "2_2") (pintype "unspecified"))
      (node (ref "R35") (pin "1") (pinfunction "1_1") (pintype "unspecified"))
      (node (ref "R39") (pin "2") (pinfunction "2_2") (pintype "unspecified"))
      (node (ref "R40") (pin "1") (pinfunction "1_1") (pintype "unspecified"))
      (node (ref "U14") (pin "1") (pinfunction "1_1") (pintype "unspecified"))
      (node (ref "U18") (pin "3") (pinfunction "IN1+_3") (pintype "unspecified"))
      (node (ref "U18") (pin "5") (pinfunction "IN2+_5") (pintype "unspecified"))
      (node (ref "U20") (pin "6") (pinfunction "REF_6") (pintype "unspecified"))
    )
    (net (code "65") (name "VTH_RPM") (class "Default")
      (node (ref "C16") (pin "1") (pinfunction "1_1") (pintype "unspecified"))
      (node (ref "RP3") (pin "2") (pinfunction "2_2") (pintype "input"))
      (node (ref "U19") (pin "2") (pinfunction "1IN-_2") (pintype "unspecified"))
      (node (ref "U21") (pin "1") (pinfunction "1_1") (pintype "unspecified"))
    )
    (net (code "66") (name "unconnected-(GSU_DEBUG_UART1-SHIELD{slash}NC-Pad4)") (class "Default")
      (node (ref "GSU_DEBUG_UART1") (pin "4") (pinfunction "SHIELD/NC_4") (pintype "unspecified"))
    )
    (net (code "67") (name "unconnected-(TMP_PIN_IN1-SHIELD{slash}NC-Pad6)") (class "Default")
      (node (ref "TMP_PIN_IN1") (pin "6") (pinfunction "SHIELD/NC_6") (pintype "unspecified"))
    )
    (net (code "68") (name "unconnected-(TMP_PIN_OUT1-SHIELD{slash}NC-Pad6)") (class "Default")
      (node (ref "TMP_PIN_OUT1") (pin "6") (pinfunction "SHIELD/NC_6") (pintype "unspecified"))
    )
    (net (code "69") (name "unconnected-(U4-BEC_5V_NC_Red-Pad2)") (class "Default")
      (node (ref "U4") (pin "2") (pinfunction "BEC_5V_NC_Red_2") (pintype "unspecified"))
    )
    (net (code "70") (name "unconnected-(U5-CLK-Pad20)") (class "Default")
      (node (ref "U5") (pin "20") (pinfunction "CLK_20") (pintype "unspecified"))
    )
    (net (code "71") (name "unconnected-(U5-CMD-Pad18)") (class "Default")
      (node (ref "U5") (pin "18") (pinfunction "CMD_18") (pintype "unspecified"))
    )
    (net (code "72") (name "unconnected-(U5-EN-Pad2)") (class "Default")
      (node (ref "U5") (pin "2") (pinfunction "EN_2") (pintype "unspecified"))
    )
    (net (code "73") (name "unconnected-(U5-GND-Pad32)") (class "Default")
      (node (ref "U5") (pin "32") (pinfunction "GND_32") (pintype "unspecified"))
    )
    (net (code "74") (name "unconnected-(U5-P0-Pad25)") (class "Default")
      (node (ref "U5") (pin "25") (pinfunction "P0_25") (pintype "unspecified"))
    )
    (net (code "75") (name "unconnected-(U5-P2-Pad24)") (class "Default")
      (node (ref "U5") (pin "24") (pinfunction "P2_24") (pintype "unspecified"))
    )
    (net (code "76") (name "unconnected-(U5-P4-Pad26)") (class "Default")
      (node (ref "U5") (pin "26") (pinfunction "P4_26") (pintype "unspecified"))
    )
    (net (code "77") (name "unconnected-(U5-P12-Pad13)") (class "Default")
      (node (ref "U5") (pin "13") (pinfunction "P12_13") (pintype "unspecified"))
    )
    (net (code "78") (name "unconnected-(U5-P15-Pad23)") (class "Default")
      (node (ref "U5") (pin "23") (pinfunction "P15_23") (pintype "unspecified"))
    )
    (net (code "79") (name "unconnected-(U5-P21-Pad33)") (class "Default")
      (node (ref "U5") (pin "33") (pinfunction "P21_33") (pintype "unspecified"))
    )
    (net (code "80") (name "unconnected-(U5-SD0-Pad21)") (class "Default")
      (node (ref "U5") (pin "21") (pinfunction "SD0_21") (pintype "unspecified"))
    )
    (net (code "81") (name "unconnected-(U5-SD1-Pad22)") (class "Default")
      (node (ref "U5") (pin "22") (pinfunction "SD1_22") (pintype "unspecified"))
    )
    (net (code "82") (name "unconnected-(U5-SD2-Pad16)") (class "Default")
      (node (ref "U5") (pin "16") (pinfunction "SD2_16") (pintype "unspecified"))
    )
    (net (code "83") (name "unconnected-(U5-SD3-Pad17)") (class "Default")
      (node (ref "U5") (pin "17") (pinfunction "SD3_17") (pintype "unspecified"))
    )
    (net (code "84") (name "unconnected-(U5-SVN{slash}P39-Pad4)") (class "Default")
      (node (ref "U5") (pin "4") (pinfunction "SVN/P39_4") (pintype "unspecified"))
    )
    (net (code "85") (name "unconnected-(U5-SVP{slash}P36-Pad3)") (class "Default")
      (node (ref "U5") (pin "3") (pinfunction "SVP/P36_3") (pintype "unspecified"))
    )
    (net (code "86") (name "unconnected-(U8-+5V_RC_{slash}_NC-Pad2)") (class "Default")
      (node (ref "U8") (pin "2") (pinfunction "+5V_RC_/_NC_2") (pintype "unspecified"))
    )
    (net (code "87") (name "unconnected-(U9-BEC_5V_NC_Red-Pad2)") (class "Default")
      (node (ref "U9") (pin "2") (pinfunction "BEC_5V_NC_Red_2") (pintype "unspecified"))
    )
    (net (code "88") (name "unconnected-(U11-+5V_RC_{slash}_NC-Pad2)") (class "Default")
      (node (ref "U11") (pin "2") (pinfunction "+5V_RC_/_NC_2") (pintype "unspecified"))
    )
    (net (code "89") (name "unconnected-(U19-2OUT-Pad7)") (class "Default")
      (node (ref "U19") (pin "7") (pinfunction "2OUT_7") (pintype "unspecified"))
    )
  )
)
